# SAMC21_Xplained_Pro_Target_MCU.net
KiCad netlist of a schematic drawn in Altium Designer
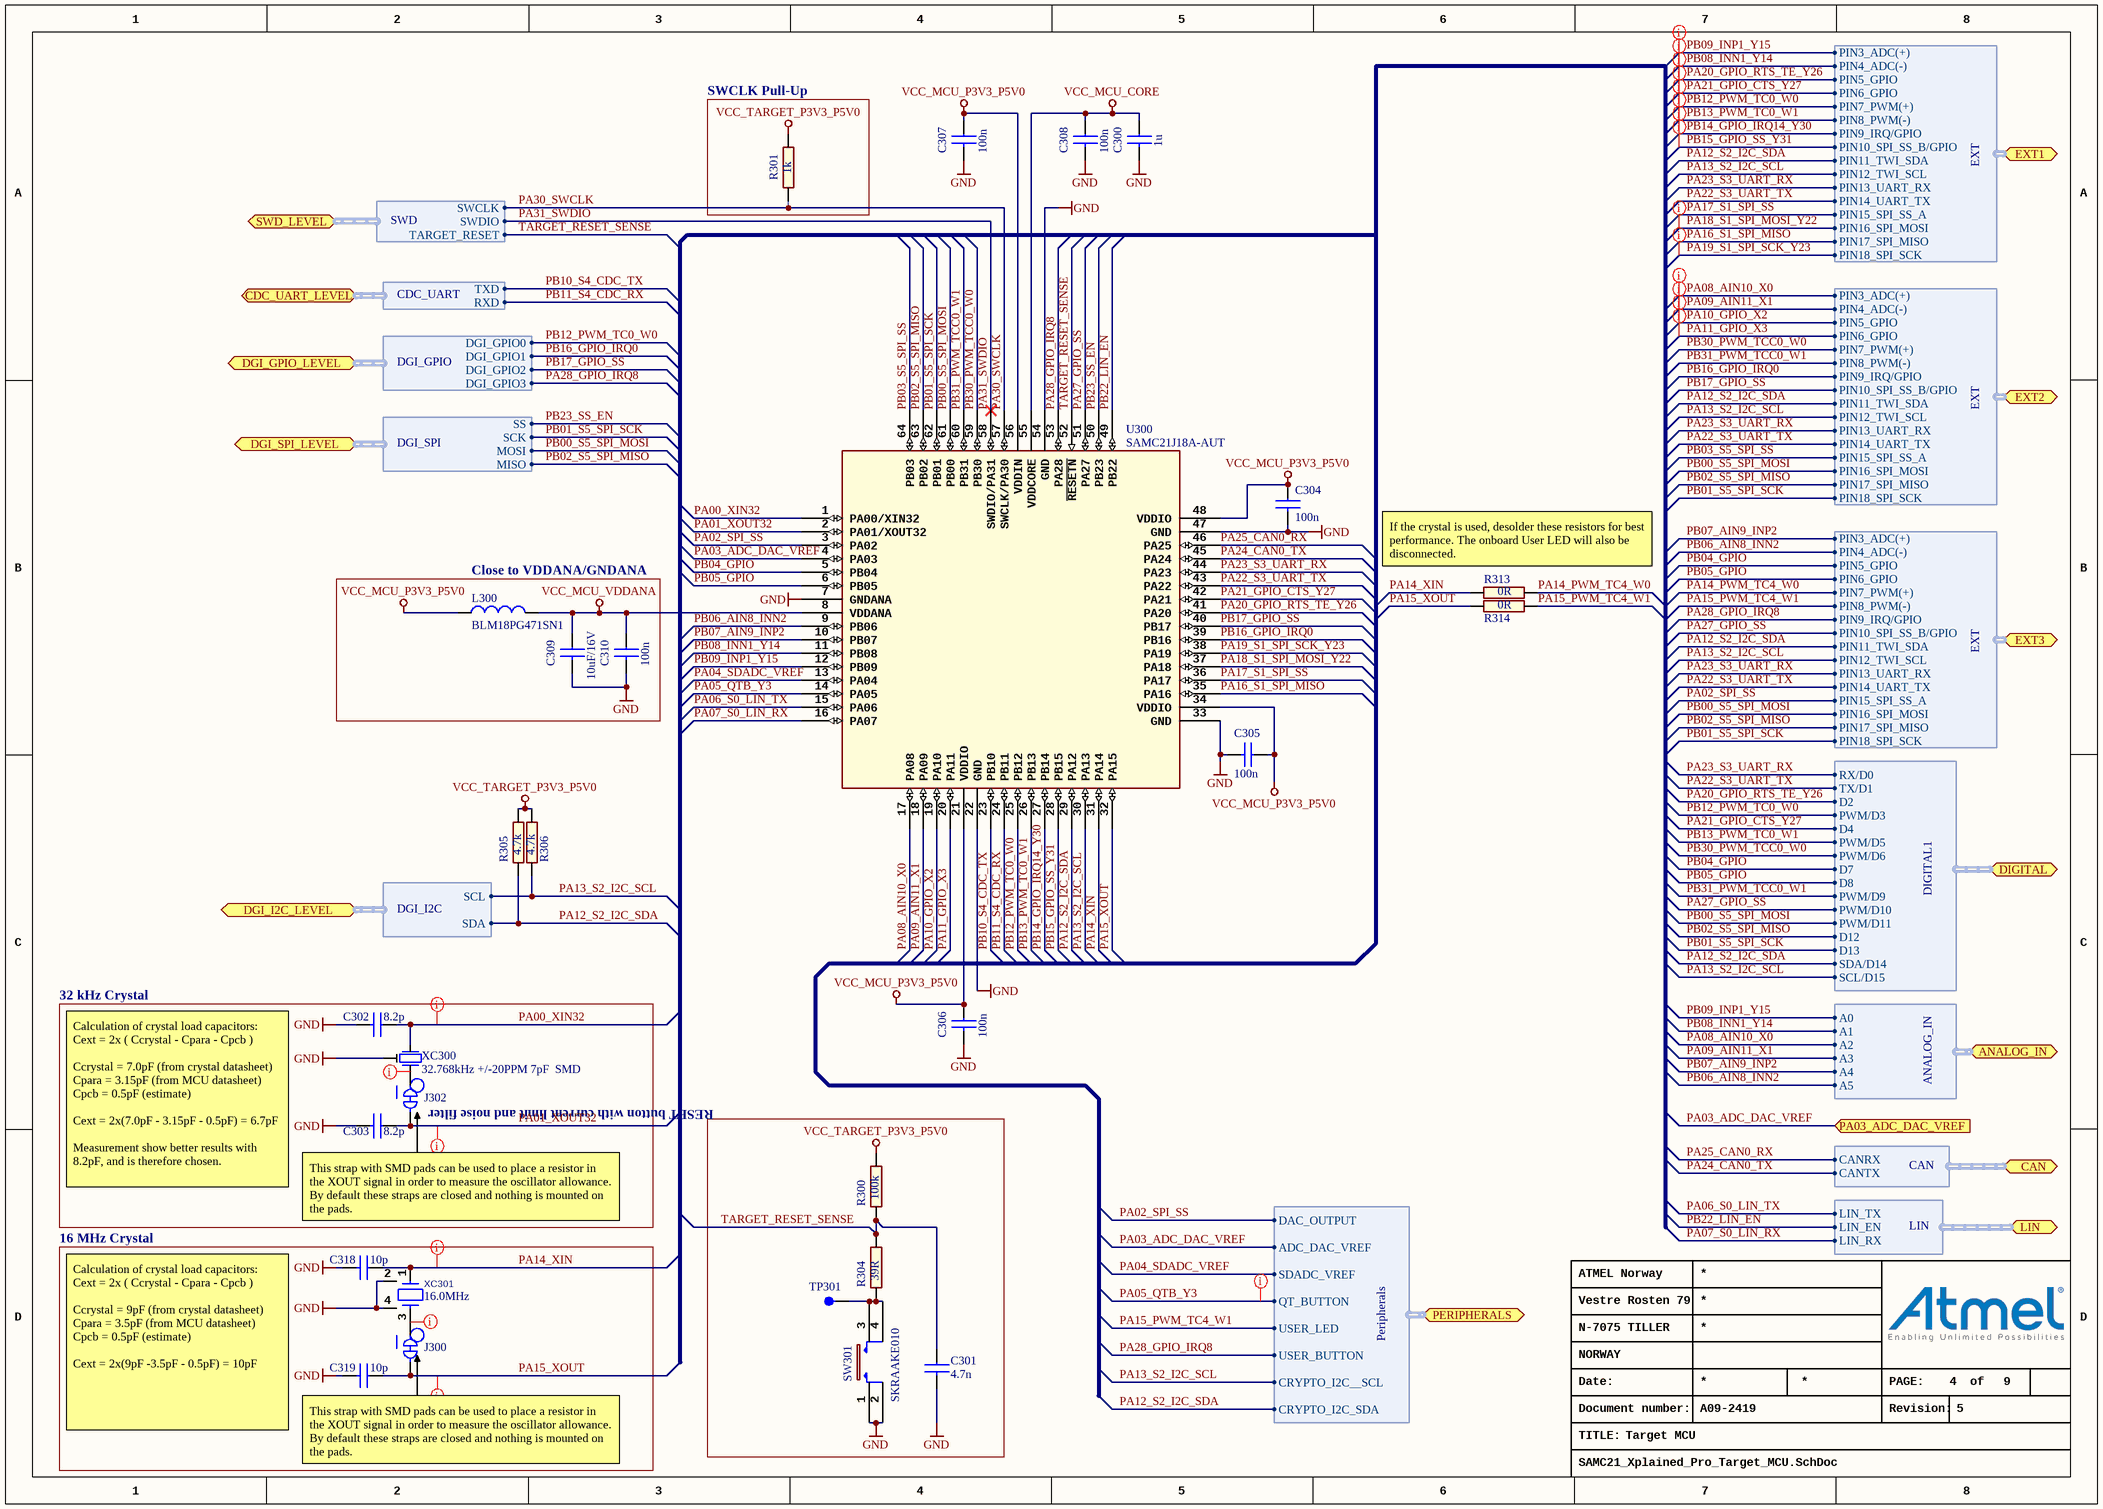
[diagram p0: SAMC21_Xplained_Pro_Target_MCU.SchDoc]

(export (version "E")
  (design (tool "Eeschema 10.0.6"))
  (components
    (comp (ref "C300")
      (value "1u")
      (footprint "AP1-00001")
      (description "Ceramic capacitor, SMD 0402, X5R, 6.3V, +/-10% (de26942)")
      (fields (field (name "TOLERANCE") "+/-10%") (field (name "MANUFACTURER") "Kemet"))
      (libsource (lib "AltiumDbLib") (part "CAP-NONPOL"))
    )
    (comp (ref "C301")
      (value "4.7n")
      (footprint "AP1-00001")
      (description "Ceramic capacitor, SMD 0402, X7R, 25V, +/-10% (de35287)")
      (fields (field (name "TOLERANCE") "25V, +/-10%"))
      (libsource (lib "AltiumDbLib") (part "CAP-NONPOL"))
    )
    (comp (ref "C302")
      (value "8.2p")
      (footprint "AP1-00001")
      (description "Ceramic capacitor, SMD 0402, NP0, 50V, +/-5%")
      (fields (field (name "TOLERANCE") "50V, +/-5%"))
      (libsource (lib "AltiumDbLib") (part "CAP-NONPOL"))
    )
    (comp (ref "C303")
      (value "8.2p")
      (footprint "AP1-00001")
      (description "Ceramic capacitor, SMD 0402, NP0, 50V, +/-5%")
      (fields (field (name "TOLERANCE") "50V, +/-5%"))
      (libsource (lib "AltiumDbLib") (part "CAP-NONPOL"))
    )
    (comp (ref "C304")
      (value "100n")
      (footprint "AP1-00001")
      (description "Ceramic capacitor, SMD 0402, X7R, 16V, +/-10%")
      (fields (field (name "TOLERANCE") "16V, +/-10%") (field (name "MANUFACTURER") "Kemet"))
      (libsource (lib "AltiumDbLib") (part "CAP-NONPOL"))
    )
    (comp (ref "C305")
      (value "100n")
      (footprint "AP1-00001")
      (description "Ceramic capacitor, SMD 0402, X7R, 16V, +/-10%")
      (fields (field (name "TOLERANCE") "16V, +/-10%") (field (name "MANUFACTURER") "Kemet"))
      (libsource (lib "AltiumDbLib") (part "CAP-NONPOL"))
    )
    (comp (ref "C306")
      (value "100n")
      (footprint "AP1-00001")
      (description "Ceramic capacitor, SMD 0402, X7R, 16V, +/-10%")
      (fields (field (name "TOLERANCE") "16V, +/-10%") (field (name "MANUFACTURER") "Kemet"))
      (libsource (lib "AltiumDbLib") (part "CAP-NONPOL"))
    )
    (comp (ref "C307")
      (value "100n")
      (footprint "AP1-00001")
      (description "Ceramic capacitor, SMD 0402, X7R, 16V, +/-10%")
      (fields (field (name "TOLERANCE") "16V, +/-10%") (field (name "MANUFACTURER") "Kemet"))
      (libsource (lib "AltiumDbLib") (part "CAP-NONPOL"))
    )
    (comp (ref "C308")
      (value "100n")
      (footprint "AP1-00001")
      (description "Ceramic capacitor, SMD 0402, X7R, 16V, +/-10%")
      (fields (field (name "TOLERANCE") "16V, +/-10%") (field (name "MANUFACTURER") "Kemet"))
      (libsource (lib "AltiumDbLib") (part "CAP-NONPOL"))
    )
    (comp (ref "C309")
      (value "10uF/16V")
      (footprint "AP1-00039")
      (description "Ceramic capacitor, SMD 0603, X5R, 16V, 10UF ± 20% (High Density)")
      (fields (field (name "MANUFACTURER") "Taiyo Yuden") (field (name "MPN") "EMK107BBJ106MA-T"))
      (libsource (lib "AltiumDbLib") (part "CAP-NONPOL"))
    )
    (comp (ref "C310")
      (value "100n")
      (footprint "AP1-00001")
      (description "Ceramic capacitor, SMD 0402, X7R, 16V, +/-10%")
      (fields (field (name "TOLERANCE") "16V, +/-10%") (field (name "MANUFACTURER") "Kemet"))
      (libsource (lib "AltiumDbLib") (part "CAP-NONPOL"))
    )
    (comp (ref "C318")
      (value "10p")
      (footprint "AP1-00001")
      (description "Ceramic capacitor, SMD 0402, NP0, 50V, +/-5%")
      (fields (field (name "TOLERANCE") "50V, +/-5%"))
      (libsource (lib "AltiumDbLib") (part "CAP-NONPOL"))
    )
    (comp (ref "C319")
      (value "10p")
      (footprint "AP1-00001")
      (description "Ceramic capacitor, SMD 0402, NP0, 50V, +/-5%")
      (fields (field (name "TOLERANCE") "50V, +/-5%"))
      (libsource (lib "AltiumDbLib") (part "CAP-NONPOL"))
    )
    (comp (ref "J300")
      (value "~")
      (footprint "AP9-00044")
      (description "Default closed SMD strap, 0603 size")
      (libsource (lib "AltiumDbLib") (part "SMD-STRAP_CLOSED"))
    )
    (comp (ref "J302")
      (value "~")
      (footprint "AP9-00044")
      (description "Default closed SMD strap, 0603 size")
      (libsource (lib "AltiumDbLib") (part "SMD-STRAP_CLOSED"))
    )
    (comp (ref "L300")
      (value "BLM18PG471SN1")
      (footprint "AP3-00005")
      (description "SMD RF inductor 0603. Z=470Ohm (@100MHz), Max R(dc)=0.65Ohm, Max current=1A")
      (fields (field (name "TOLERANCE") "±25%") (field (name "MANUFACTURER") "Murata"))
      (libsource (lib "AltiumDbLib") (part "INDUCTOR"))
    )
    (comp (ref "R300")
      (value "100k")
      (footprint "AP2-00011")
      (description "Thick film resistor, SMD 0402, 1/16W, 1%")
      (fields (field (name "TOLERANCE") "1 %"))
      (libsource (lib "AltiumDbLib") (part "R2"))
    )
    (comp (ref "R301")
      (value "1k")
      (footprint "AP2-00000")
      (description "Thick film resistor, SMD 0402, 1/16W, 1%")
      (fields (field (name "TOLERANCE") "1 %"))
      (libsource (lib "AltiumDbLib") (part "R2"))
    )
    (comp (ref "R304")
      (value "39R")
      (footprint "AP2-00011")
      (description "Thick film resistor, SMD 0402, 1/16W, 1%")
      (fields (field (name "TOLERANCE") "1 %"))
      (libsource (lib "") (part "R2_1"))
    )
    (comp (ref "R305")
      (value "4.7k")
      (footprint "AP2-00000")
      (description "Thick film resistor, SMD 0402, 1/16W, 1%")
      (fields (field (name "TOLERANCE") "1 %"))
      (libsource (lib "AltiumDbLib") (part "R2"))
    )
    (comp (ref "R306")
      (value "4.7k")
      (footprint "AP2-00000")
      (description "Thick film resistor, SMD 0402, 1/16W, 1%")
      (fields (field (name "TOLERANCE") "1 %"))
      (libsource (lib "AltiumDbLib") (part "R2"))
    )
    (comp (ref "R313")
      (value "0R")
      (footprint "AP2-00000")
      (description "Thick film resistor, SMD 0402, 1/16W, 1%")
      (fields (field (name "TOLERANCE") "1 %") (field (name "MANUFACTURER") "(n/a)"))
      (libsource (lib "") (part "R2_2"))
    )
    (comp (ref "R314")
      (value "0R")
      (footprint "AP2-00000")
      (description "Thick film resistor, SMD 0402, 1/16W, 1%")
      (fields (field (name "TOLERANCE") "1 %") (field (name "MANUFACTURER") "(n/a)"))
      (libsource (lib "") (part "R2_2"))
    )
    (comp (ref "SW301")
      (value "SKRAAKE010")
      (footprint "AP8-00137")
      (description "6.2x6.2 mm SMD tact switch, same as A08-0091 but less force is needed")
      (fields
        (field (name "MANUFACTURER") "ALPS")
        (field (name "Comment") "same as A08-0091 but less force is needed; Can be ordered in low volumes from Mouser")
      )
      (libsource (lib "AltiumDbLib") (part "PUSHBUTTON1"))
    )
    (comp (ref "TP301")
      (value "~")
      (footprint "AP8-00010")
      (description "Single SMD testpad")
      (libsource (lib "AltiumDbLib") (part "TESTPOINT"))
    )
    (comp (ref "U300")
      (value "SAMC21J18A-AUT")
      (footprint "AP6-00173")
      (description "Atmel 32-bit RISC MCU 64pin")
      (fields (field (name "MANUFACTURER") "ATMEL"))
      (libsource (lib "AltiumDbLib") (part "SAMC21J_TQFP64"))
    )
    (comp (ref "XC300")
      (value "32.768kHz +/-20PPM 7pF  SMD")
      (footprint "AP7-00044")
      (description "32k768 crystal, +-20ppm, CL=7pF, max ESR 60kOhm, SMD")
      (fields (field (name "TOLERANCE") "+/- 20 PPM") (field (name "MANUFACTURER") "Micro Crystal"))
      (libsource (lib "AltiumDbLib") (part "CRYSTAL_2P_metal"))
    )
    (comp (ref "XC301")
      (value "16.0MHz")
      (footprint "AP7-00061")
      (description "16MHz uXtal, 3.2 x 2.5 mm SMD, CL=9pF, 15PPM, ESR=80ohm(Max.")
      (fields (field (name "TOLERANCE") "15ppm") (field (name "MANUFACTURER") "Epson Toyocom"))
      (libsource (lib "AltiumDbLib") (part "TSX-3225"))
    )
  )
  (nets
    (net (code "12") (name "/PA00_XIN32") (class "Default")
      (node (ref "C302") (pin "1") (pinfunction "1_1") (pintype "passive"))
      (node (ref "U300") (pin "1") (pinfunction "PA00/XIN32_1") (pintype "bidirectional"))
      (node (ref "XC300") (pin "2") (pinfunction "2_2") (pintype "passive"))
    )
    (net (code "13") (name "/PA01_XOUT32") (class "Default")
      (node (ref "C303") (pin "1") (pinfunction "1_1") (pintype "passive"))
      (node (ref "J302") (pin "2") (pinfunction "2_2") (pintype "passive"))
      (node (ref "U300") (pin "2") (pinfunction "PA01/XOUT32_2") (pintype "bidirectional"))
    )
    (net (code "14") (name "/PA02_SPI_SS") (class "Default")
      (node (ref "U300") (pin "3") (pinfunction "PA02_3") (pintype "bidirectional"))
    )
    (net (code "15") (name "/PA03_ADC_DAC_VREF") (class "Default")
      (node (ref "U300") (pin "4") (pinfunction "PA03_4") (pintype "bidirectional"))
    )
    (net (code "16") (name "/PA04_SDADC_VREF") (class "Default")
      (node (ref "U300") (pin "13") (pinfunction "PA04_13") (pintype "bidirectional"))
    )
    (net (code "17") (name "/PA05_QTB_Y3") (class "Default")
      (node (ref "U300") (pin "14") (pinfunction "PA05_14") (pintype "bidirectional"))
    )
    (net (code "18") (name "/PA06_S0_LIN_TX") (class "Default")
      (node (ref "U300") (pin "15") (pinfunction "PA06_15") (pintype "bidirectional"))
    )
    (net (code "19") (name "/PA07_S0_LIN_RX") (class "Default")
      (node (ref "U300") (pin "16") (pinfunction "PA07_16") (pintype "bidirectional"))
    )
    (net (code "20") (name "/PA08_AIN10_X0") (class "Default")
      (node (ref "U300") (pin "17") (pinfunction "PA08_17") (pintype "bidirectional"))
    )
    (net (code "21") (name "/PA09_AIN11_X1") (class "Default")
      (node (ref "U300") (pin "18") (pinfunction "PA09_18") (pintype "bidirectional"))
    )
    (net (code "22") (name "/PA10_GPIO_X2") (class "Default")
      (node (ref "U300") (pin "19") (pinfunction "PA10_19") (pintype "bidirectional"))
    )
    (net (code "23") (name "/PA11_GPIO_X3") (class "Default")
      (node (ref "U300") (pin "20") (pinfunction "PA11_20") (pintype "bidirectional"))
    )
    (net (code "24") (name "/PA12_S2_I2C_SDA") (class "Default")
      (node (ref "R305") (pin "1") (pinfunction "1_1") (pintype "passive"))
      (node (ref "U300") (pin "29") (pinfunction "PA12_29") (pintype "bidirectional"))
    )
    (net (code "25") (name "/PA13_S2_I2C_SCL") (class "Default")
      (node (ref "R306") (pin "1") (pinfunction "1_1") (pintype "passive"))
      (node (ref "U300") (pin "30") (pinfunction "PA13_30") (pintype "bidirectional"))
    )
    (net (code "26") (name "/PA14_PWM_TC4_W0") (class "Default")
      (node (ref "R313") (pin "2") (pinfunction "2_2") (pintype "passive"))
    )
    (net (code "27") (name "/PA14_XIN") (class "Default")
      (node (ref "C318") (pin "1") (pinfunction "1_1") (pintype "passive"))
      (node (ref "R313") (pin "1") (pinfunction "1_1") (pintype "passive"))
      (node (ref "U300") (pin "31") (pinfunction "PA14_31") (pintype "bidirectional"))
      (node (ref "XC301") (pin "1") (pinfunction "IN_1") (pintype "passive"))
    )
    (net (code "28") (name "/PA15_PWM_TC4_W1") (class "Default")
      (node (ref "R314") (pin "2") (pinfunction "2_2") (pintype "passive"))
    )
    (net (code "29") (name "/PA15_XOUT") (class "Default")
      (node (ref "C319") (pin "1") (pinfunction "1_1") (pintype "passive"))
      (node (ref "J300") (pin "2") (pinfunction "2_2") (pintype "passive"))
      (node (ref "R314") (pin "1") (pinfunction "1_1") (pintype "passive"))
      (node (ref "U300") (pin "32") (pinfunction "PA15_32") (pintype "bidirectional"))
    )
    (net (code "30") (name "/PA16_S1_SPI_MISO") (class "Default")
      (node (ref "U300") (pin "35") (pinfunction "PA16_35") (pintype "bidirectional"))
    )
    (net (code "31") (name "/PA17_S1_SPI_SS") (class "Default")
      (node (ref "U300") (pin "36") (pinfunction "PA17_36") (pintype "bidirectional"))
    )
    (net (code "32") (name "/PA18_S1_SPI_MOSI_Y22") (class "Default")
      (node (ref "U300") (pin "37") (pinfunction "PA18_37") (pintype "bidirectional"))
    )
    (net (code "33") (name "/PA19_S1_SPI_SCK_Y23") (class "Default")
      (node (ref "U300") (pin "38") (pinfunction "PA19_38") (pintype "bidirectional"))
    )
    (net (code "34") (name "/PA20_GPIO_RTS_TE_Y26") (class "Default")
      (node (ref "U300") (pin "41") (pinfunction "PA20_41") (pintype "bidirectional"))
    )
    (net (code "35") (name "/PA21_GPIO_CTS_Y27") (class "Default")
      (node (ref "U300") (pin "42") (pinfunction "PA21_42") (pintype "bidirectional"))
    )
    (net (code "36") (name "/PA22_S3_UART_TX") (class "Default")
      (node (ref "U300") (pin "43") (pinfunction "PA22_43") (pintype "bidirectional"))
    )
    (net (code "37") (name "/PA23_S3_UART_RX") (class "Default")
      (node (ref "U300") (pin "44") (pinfunction "PA23_44") (pintype "bidirectional"))
    )
    (net (code "38") (name "/PA24_CAN0_TX") (class "Default")
      (node (ref "U300") (pin "45") (pinfunction "PA24_45") (pintype "bidirectional"))
    )
    (net (code "39") (name "/PA25_CAN0_RX") (class "Default")
      (node (ref "U300") (pin "46") (pinfunction "PA25_46") (pintype "bidirectional"))
    )
    (net (code "40") (name "/PA27_GPIO_SS") (class "Default")
      (node (ref "U300") (pin "51") (pinfunction "PA27_51") (pintype "bidirectional"))
    )
    (net (code "41") (name "/PA28_GPIO_IRQ8") (class "Default")
      (node (ref "U300") (pin "53") (pinfunction "PA28_53") (pintype "bidirectional"))
    )
    (net (code "42") (name "/PA30_SWCLK") (class "Default")
      (node (ref "R301") (pin "1") (pinfunction "1_1") (pintype "passive"))
      (node (ref "U300") (pin "57") (pinfunction "SWCLK/PA30_57") (pintype "bidirectional"))
    )
    (net (code "43") (name "/PA31_SWDIO") (class "Default")
      (node (ref "U300") (pin "58") (pinfunction "SWDIO/PA31_58") (pintype "bidirectional+no_connect"))
    )
    (net (code "44") (name "/PB00_S5_SPI_MOSI") (class "Default")
      (node (ref "U300") (pin "61") (pinfunction "PB00_61") (pintype "bidirectional"))
    )
    (net (code "45") (name "/PB01_S5_SPI_SCK") (class "Default")
      (node (ref "U300") (pin "62") (pinfunction "PB01_62") (pintype "bidirectional"))
    )
    (net (code "46") (name "/PB02_S5_SPI_MISO") (class "Default")
      (node (ref "U300") (pin "63") (pinfunction "PB02_63") (pintype "bidirectional"))
    )
    (net (code "47") (name "/PB03_S5_SPI_SS") (class "Default")
      (node (ref "U300") (pin "64") (pinfunction "PB03_64") (pintype "bidirectional"))
    )
    (net (code "48") (name "/PB04_GPIO") (class "Default")
      (node (ref "U300") (pin "5") (pinfunction "PB04_5") (pintype "bidirectional"))
    )
    (net (code "49") (name "/PB05_GPIO") (class "Default")
      (node (ref "U300") (pin "6") (pinfunction "PB05_6") (pintype "bidirectional"))
    )
    (net (code "50") (name "/PB06_AIN8_INN2") (class "Default")
      (node (ref "U300") (pin "9") (pinfunction "PB06_9") (pintype "bidirectional"))
    )
    (net (code "51") (name "/PB07_AIN9_INP2") (class "Default")
      (node (ref "U300") (pin "10") (pinfunction "PB07_10") (pintype "bidirectional"))
    )
    (net (code "52") (name "/PB08_INN1_Y14") (class "Default")
      (node (ref "U300") (pin "11") (pinfunction "PB08_11") (pintype "bidirectional"))
    )
    (net (code "53") (name "/PB09_INP1_Y15") (class "Default")
      (node (ref "U300") (pin "12") (pinfunction "PB09_12") (pintype "bidirectional"))
    )
    (net (code "54") (name "/PB10_S4_CDC_TX") (class "Default")
      (node (ref "U300") (pin "23") (pinfunction "PB10_23") (pintype "bidirectional"))
    )
    (net (code "55") (name "/PB11_S4_CDC_RX") (class "Default")
      (node (ref "U300") (pin "24") (pinfunction "PB11_24") (pintype "bidirectional"))
    )
    (net (code "56") (name "/PB12_PWM_TC0_W0") (class "Default")
      (node (ref "U300") (pin "25") (pinfunction "PB12_25") (pintype "bidirectional"))
    )
    (net (code "57") (name "/PB13_PWM_TC0_W1") (class "Default")
      (node (ref "U300") (pin "26") (pinfunction "PB13_26") (pintype "bidirectional"))
    )
    (net (code "58") (name "/PB14_GPIO_IRQ14_Y30") (class "Default")
      (node (ref "U300") (pin "27") (pinfunction "PB14_27") (pintype "bidirectional"))
    )
    (net (code "59") (name "/PB15_GPIO_SS_Y31") (class "Default")
      (node (ref "U300") (pin "28") (pinfunction "PB15_28") (pintype "bidirectional"))
    )
    (net (code "60") (name "/PB16_GPIO_IRQ0") (class "Default")
      (node (ref "U300") (pin "39") (pinfunction "PB16_39") (pintype "bidirectional"))
    )
    (net (code "61") (name "/PB17_GPIO_SS") (class "Default")
      (node (ref "U300") (pin "40") (pinfunction "PB17_40") (pintype "bidirectional"))
    )
    (net (code "62") (name "/PB22_LIN_EN") (class "Default")
      (node (ref "U300") (pin "49") (pinfunction "PB22_49") (pintype "bidirectional"))
    )
    (net (code "63") (name "/PB23_SS_EN") (class "Default")
      (node (ref "U300") (pin "50") (pinfunction "PB23_50") (pintype "bidirectional"))
    )
    (net (code "64") (name "/PB30_PWM_TCC0_W0") (class "Default")
      (node (ref "U300") (pin "59") (pinfunction "PB30_59") (pintype "bidirectional"))
    )
    (net (code "65") (name "/PB31_PWM_TCC0_W1") (class "Default")
      (node (ref "U300") (pin "60") (pinfunction "PB31_60") (pintype "bidirectional"))
    )
    (net (code "66") (name "/TARGET_RESET_SENSE") (class "Default")
      (node (ref "C301") (pin "1") (pinfunction "1_1") (pintype "passive"))
      (node (ref "R300") (pin "1") (pinfunction "1_1") (pintype "passive"))
      (node (ref "R304") (pin "2") (pinfunction "2_2") (pintype "passive"))
      (node (ref "U300") (pin "52") (pinfunction "~{RESETN}_52") (pintype "input"))
    )
    (net (code "78") (name "GND") (class "Default")
      (node (ref "C300") (pin "2") (pinfunction "2_2") (pintype "passive"))
      (node (ref "C301") (pin "2") (pinfunction "2_2") (pintype "passive"))
      (node (ref "C302") (pin "2") (pinfunction "2_2") (pintype "passive"))
      (node (ref "C303") (pin "2") (pinfunction "2_2") (pintype "passive"))
      (node (ref "C304") (pin "2") (pinfunction "2_2") (pintype "passive"))
      (node (ref "C305") (pin "2") (pinfunction "2_2") (pintype "passive"))
      (node (ref "C306") (pin "2") (pinfunction "2_2") (pintype "passive"))
      (node (ref "C307") (pin "2") (pinfunction "2_2") (pintype "passive"))
      (node (ref "C308") (pin "2") (pinfunction "2_2") (pintype "passive"))
      (node (ref "C309") (pin "2") (pinfunction "2_2") (pintype "passive"))
      (node (ref "C310") (pin "2") (pinfunction "2_2") (pintype "passive"))
      (node (ref "C318") (pin "2") (pinfunction "2_2") (pintype "passive"))
      (node (ref "C319") (pin "2") (pinfunction "2_2") (pintype "passive"))
      (node (ref "SW301") (pin "1") (pinfunction "1_1") (pintype "passive"))
      (node (ref "SW301") (pin "2") (pinfunction "2_2") (pintype "passive"))
      (node (ref "U300") (pin "22") (pinfunction "GND_22") (pintype "power_in"))
      (node (ref "U300") (pin "33") (pinfunction "GND_33") (pintype "power_in"))
      (node (ref "U300") (pin "47") (pinfunction "GND_47") (pintype "power_in"))
      (node (ref "U300") (pin "54") (pinfunction "GND_54") (pintype "power_in"))
      (node (ref "U300") (pin "7") (pinfunction "GNDANA_7") (pintype "power_in"))
      (node (ref "XC300") (pin "3") (pinfunction "3_3") (pintype "passive"))
      (node (ref "XC301") (pin "2") (pinfunction "GND_2") (pintype "passive"))
      (node (ref "XC301") (pin "4") (pinfunction "GND_4") (pintype "passive"))
    )
    (net (code "79") (name "Net-(J302-Pad1)") (class "Default")
      (node (ref "J302") (pin "1") (pinfunction "1_1") (pintype "passive"))
      (node (ref "XC300") (pin "1") (pinfunction "1_1") (pintype "passive"))
    )
    (net (code "80") (name "Net-(R304-Pad1)") (class "Default")
      (node (ref "R304") (pin "1") (pinfunction "1_1") (pintype "passive"))
      (node (ref "SW301") (pin "3") (pinfunction "3_3") (pintype "passive"))
      (node (ref "SW301") (pin "4") (pinfunction "4_4") (pintype "passive"))
      (node (ref "TP301") (pin "1") (pinfunction "1_1") (pintype "passive"))
    )
    (net (code "81") (name "Net-(XC301-OUT)") (class "Default")
      (node (ref "J300") (pin "1") (pinfunction "1_1") (pintype "passive"))
      (node (ref "XC301") (pin "3") (pinfunction "OUT_3") (pintype "passive"))
    )
    (net (code "82") (name "VCC_MCU_CORE") (class "Default")
      (node (ref "C300") (pin "1") (pinfunction "1_1") (pintype "passive"))
      (node (ref "C308") (pin "1") (pinfunction "1_1") (pintype "passive"))
      (node (ref "U300") (pin "55") (pinfunction "VDDCORE_55") (pintype "power_in"))
    )
    (net (code "83") (name "VCC_MCU_P3V3_P5V0") (class "Default")
      (node (ref "C304") (pin "1") (pinfunction "1_1") (pintype "passive"))
      (node (ref "C305") (pin "1") (pinfunction "1_1") (pintype "passive"))
      (node (ref "C306") (pin "1") (pinfunction "1_1") (pintype "passive"))
      (node (ref "C307") (pin "1") (pinfunction "1_1") (pintype "passive"))
      (node (ref "L300") (pin "1") (pinfunction "1_1") (pintype "passive"))
      (node (ref "U300") (pin "21") (pinfunction "VDDIO_21") (pintype "power_in"))
      (node (ref "U300") (pin "34") (pinfunction "VDDIO_34") (pintype "power_in"))
      (node (ref "U300") (pin "48") (pinfunction "VDDIO_48") (pintype "power_in"))
      (node (ref "U300") (pin "56") (pinfunction "VDDIN_56") (pintype "power_in"))
    )
    (net (code "84") (name "VCC_MCU_VDDANA") (class "Default")
      (node (ref "C309") (pin "1") (pinfunction "1_1") (pintype "passive"))
      (node (ref "C310") (pin "1") (pinfunction "1_1") (pintype "passive"))
      (node (ref "L300") (pin "2") (pinfunction "2_2") (pintype "passive"))
      (node (ref "U300") (pin "8") (pinfunction "VDDANA_8") (pintype "power_in"))
    )
    (net (code "85") (name "VCC_TARGET_P3V3_P5V0") (class "Default")
      (node (ref "R300") (pin "2") (pinfunction "2_2") (pintype "passive"))
      (node (ref "R301") (pin "2") (pinfunction "2_2") (pintype "passive"))
      (node (ref "R305") (pin "2") (pinfunction "2_2") (pintype "passive"))
      (node (ref "R306") (pin "2") (pinfunction "2_2") (pintype "passive"))
    )
  )
)
